# 02_POWER_BEEP_IrDA.net
KiCad netlist of a schematic drawn in Altium Designer
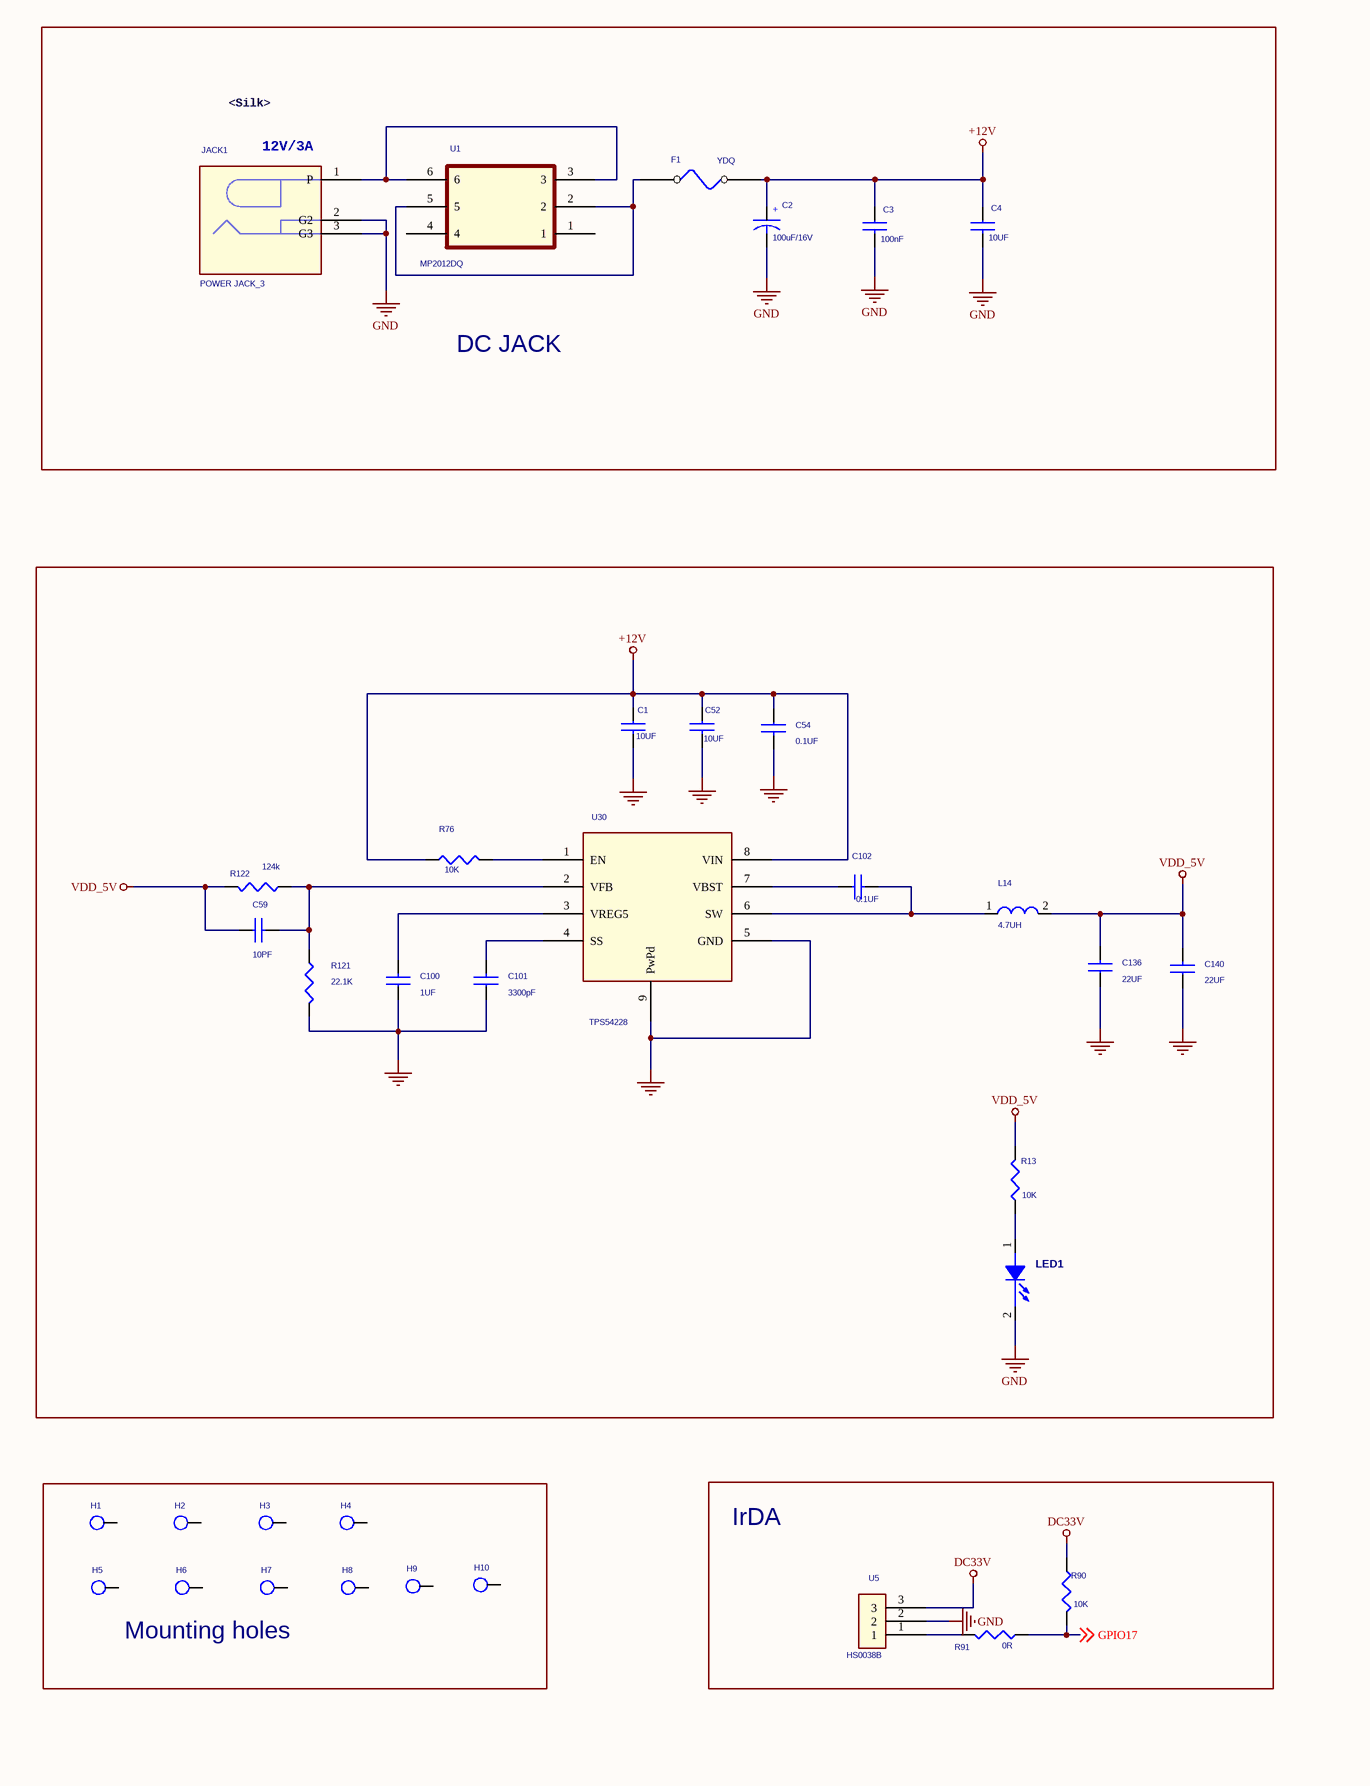
[diagram p0: 02 POWER,BEEP,IrDA.SchDoc, left]
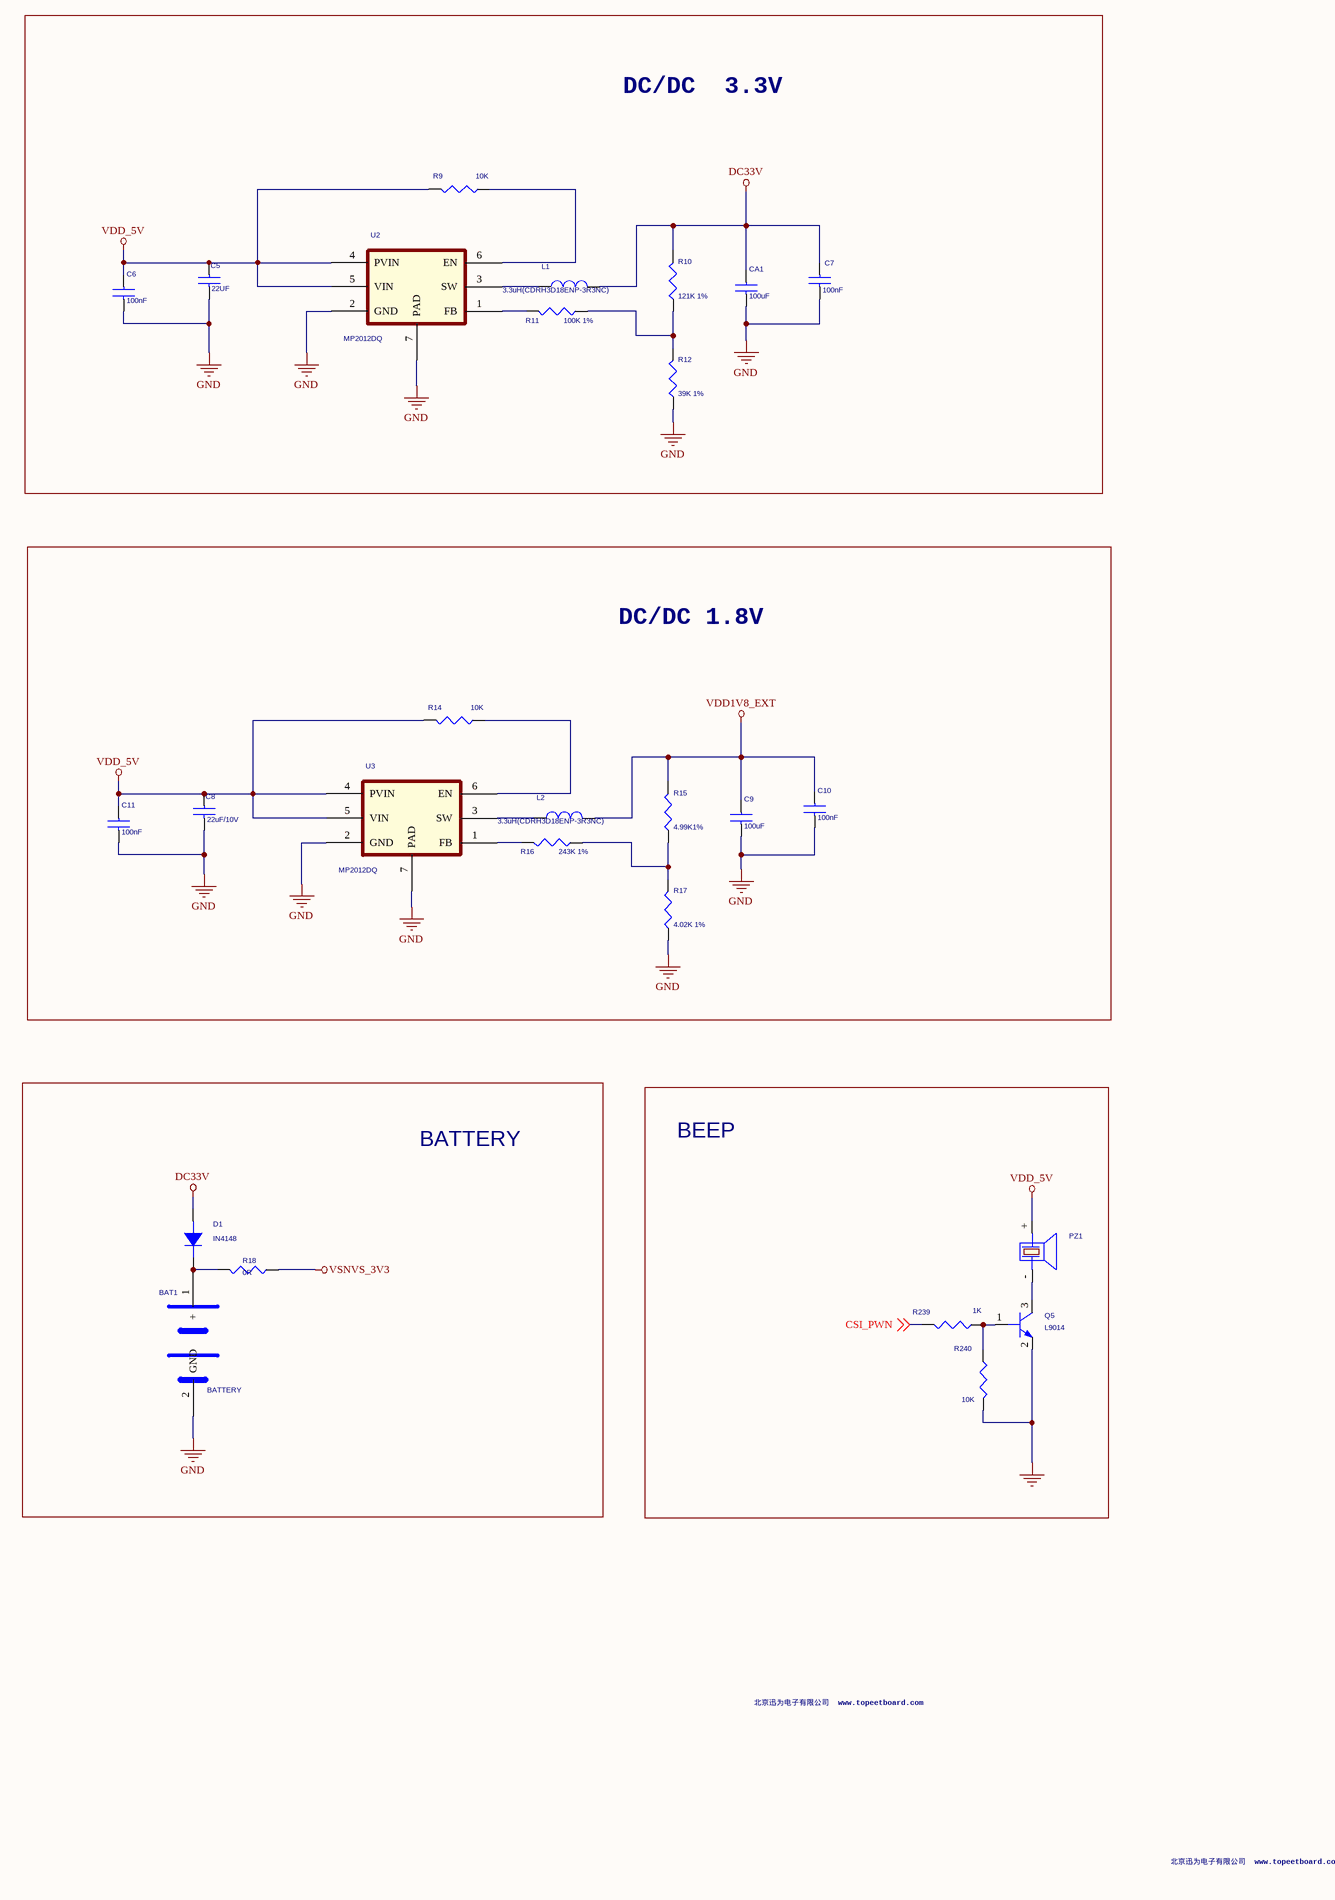
[diagram p1: 02 POWER,BEEP,IrDA.SchDoc, right]

(export (version "E")
  (design (tool "Eeschema 10.0.6"))
  (components
    (comp (ref "BAT1") (value "BATTERY") (footprint "BATTERY") (libsource (lib "*") (part "BATTERY_0")))
    (comp (ref "C1") (value "10UF") (libsource (lib "*") (part "CAP NP")))
    (comp (ref "C2") (value "100uF/16V") (footprint "T2012") (libsource (lib "*") (part "CT2012_0")))
    (comp (ref "C3") (value "100nF") (footprint "C1608") (libsource (lib "*") (part "C1608_Dup2")))
    (comp (ref "C4") (value "10UF") (footprint "C1608") (libsource (lib "*") (part "C1608_Dup2")))
    (comp (ref "C5") (value "22UF") (footprint "1206-A") (libsource (lib "*") (part "C1206_0")))
    (comp (ref "C6") (value "100nF") (footprint "C1608") (libsource (lib "*") (part "C1608_Dup2")))
    (comp (ref "C7") (value "100nF") (footprint "C1608") (libsource (lib "*") (part "C1608_Dup2")))
    (comp (ref "C8") (value "22uF/10V") (footprint "1206-A") (libsource (lib "*") (part "C1206_0")))
    (comp (ref "C9") (value "100uF") (footprint "C1608") (libsource (lib "*") (part "C1608_Dup2")))
    (comp (ref "C10") (value "100nF") (footprint "C1608") (libsource (lib "*") (part "C1608_Dup2")))
    (comp (ref "C11") (value "100nF") (footprint "C1608") (libsource (lib "*") (part "C1608_Dup2")))
    (comp (ref "C52") (value "10UF") (libsource (lib "*") (part "CAP NP")))
    (comp (ref "C54") (value "0.1UF") (libsource (lib "*") (part "CAP NP")))
    (comp (ref "C59") (value "10PF") (libsource (lib "*") (part "CAP NP")))
    (comp (ref "C100") (value "1UF") (libsource (lib "*") (part "CAP NP")))
    (comp (ref "C101") (value "3300pF") (libsource (lib "*") (part "CAP NP")))
    (comp (ref "C102") (value "0.1UF") (libsource (lib "*") (part "CAP NP")))
    (comp (ref "C136") (value "22UF") (libsource (lib "*") (part "CAP NP")))
    (comp (ref "C140") (value "22UF") (libsource (lib "*") (part "CAP NP")))
    (comp (ref "CA1") (value "100uF") (footprint "C1608") (libsource (lib "*") (part "C1608_Dup2")))
    (comp (ref "D1") (value "IN4148") (libsource (lib "*") (part "DIODE")))
    (comp (ref "F1") (value "YDQ") (libsource (lib "*") (part "FUSE")))
    (comp (ref "H1") (value "TP_P0_0.8_D0") (footprint "TP_08") (libsource (lib "*") (part "TP_P0_0.8_D0")))
    (comp (ref "H2") (value "TP_P0_0.8_D0") (footprint "TP_08") (libsource (lib "*") (part "TP_P0_0.8_D0")))
    (comp (ref "H3") (value "TP_P0_0.8_D0") (footprint "TP_08") (libsource (lib "*") (part "TP_P0_0.8_D0")))
    (comp (ref "H4") (value "TP_P0_0.8_D0") (footprint "TP_08") (libsource (lib "*") (part "TP_P0_0.8_D0")))
    (comp (ref "H5") (value "TP_P0_0.8_D0") (footprint "TP_08") (libsource (lib "*") (part "TP_P0_0.8_D0")))
    (comp (ref "H6") (value "TP_P0_0.8_D0") (footprint "TP_08") (libsource (lib "*") (part "TP_P0_0.8_D0")))
    (comp (ref "H7") (value "TP_P0_0.8_D0") (footprint "TP_08") (libsource (lib "*") (part "TP_P0_0.8_D0")))
    (comp (ref "H8") (value "TP_P0_0.8_D0") (footprint "TP_08") (libsource (lib "*") (part "TP_P0_0.8_D0")))
    (comp (ref "H9") (value "TP_P0_0.8_D0") (footprint "TP_08") (libsource (lib "*") (part "TP_P0_0.8_D0")))
    (comp (ref "H10") (value "TP_P0_0.8_D0") (footprint "TP_08") (libsource (lib "*") (part "TP_P0_0.8_D0")))
    (comp (ref "JACK1") (value "POWER JACK_3") (libsource (lib "*") (part "POWER JACK_3")))
    (comp (ref "L1")
      (value "3.3uH(CDRH3D18ENP-3R3NC)")
      (footprint "LQH32C")
      (libsource (lib "*") (part "LQH32C_0_Dup2"))
    )
    (comp (ref "L2")
      (value "3.3uH(CDRH3D18ENP-3R3NC)")
      (footprint "LQH32C")
      (libsource (lib "*") (part "LQH32C_0_Dup2"))
    )
    (comp (ref "L14") (value "4.7UH") (footprint "LQH32C") (libsource (lib "*") (part "LQH32C_0_Dup1")))
    (comp (ref "LED1")
      (value "LED-Red (SMD 2012)")
      (footprint "LED-3216")
      (libsource (lib "*") (part "LED-RED_SMD_1"))
    )
    (comp (ref "PZ1") (value "PIEZO BUZZER_2") (libsource (lib "*") (part "PIEZO BUZZER_2")))
    (comp (ref "Q5") (value "L9014") (libsource (lib "*") (part "L14P2/TO_1")))
    (comp (ref "R9") (value "10K") (footprint "R1005") (libsource (lib "*") (part "R1005_0_Dup2")))
    (comp (ref "R10") (value "121K 1%") (footprint "R1005") (libsource (lib "*") (part "R1005_0_Dup2")))
    (comp (ref "R11") (value "100K 1%") (footprint "R1005") (libsource (lib "*") (part "R1005_0_Dup2")))
    (comp (ref "R12") (value "39K 1%") (footprint "R1005") (libsource (lib "*") (part "R1005_0_Dup2")))
    (comp (ref "R13") (value "10K") (footprint "R1005") (libsource (lib "*") (part "R1005_0_Dup2")))
    (comp (ref "R14") (value "10K") (footprint "R1005") (libsource (lib "*") (part "R1005_0_Dup2")))
    (comp (ref "R15") (value "4.99K1%") (footprint "R1005") (libsource (lib "*") (part "R1005_0_Dup2")))
    (comp (ref "R16") (value "243K 1%") (footprint "R1005") (libsource (lib "*") (part "R1005_0_Dup2")))
    (comp (ref "R17") (value "4.02K 1%") (footprint "R1005") (libsource (lib "*") (part "R1005_0_Dup2")))
    (comp (ref "R18") (value "0R") (libsource (lib "*") (part "R_Dup1")))
    (comp (ref "R76") (value "10K") (libsource (lib "*") (part "R_Dup1")))
    (comp (ref "R90") (value "10K") (libsource (lib "*") (part "R_Dup1")))
    (comp (ref "R91") (value "0R") (libsource (lib "*") (part "R_Dup1")))
    (comp (ref "R121") (value "22.1K") (libsource (lib "*") (part "R_Dup1")))
    (comp (ref "R122") (value "124k") (libsource (lib "*") (part "R_Dup1")))
    (comp (ref "R239") (value "1K") (libsource (lib "*") (part "R_Dup1")))
    (comp (ref "R240") (value "10K") (libsource (lib "*") (part "R_Dup1")))
    (comp (ref "U1") (value "MP2012DQ") (footprint "QFN6") (libsource (lib "*") (part "U-MP2012DQ_0")))
    (comp (ref "U2") (value "MP2012DQ") (footprint "QFN6") (libsource (lib "*") (part "U-MP2012DQ")))
    (comp (ref "U3") (value "MP2012DQ") (footprint "QFN6") (libsource (lib "*") (part "U-MP2012DQ")))
    (comp (ref "U5") (value "HS0038B") (libsource (lib "*") (part "HS0038")))
    (comp (ref "U30") (value "TPS54228") (libsource (lib "*") (part "RT8065_5")))
  )
  (nets
    (net (code "1") (name "+12V") (class "Default")
      (node (ref "C1") (pin "1") (pinfunction "1_1") (pintype "passive"))
      (node (ref "C2") (pin "1") (pinfunction "1_1") (pintype "passive"))
      (node (ref "C3") (pin "1") (pinfunction "1_1") (pintype "passive"))
      (node (ref "C4") (pin "1") (pinfunction "1_1") (pintype "passive"))
      (node (ref "C52") (pin "1") (pinfunction "1_1") (pintype "passive"))
      (node (ref "C54") (pin "1") (pinfunction "1_1") (pintype "passive"))
      (node (ref "F1") (pin "2") (pinfunction "2_2") (pintype "passive"))
      (node (ref "R76") (pin "1") (pinfunction "1_1") (pintype "passive"))
      (node (ref "U30") (pin "8") (pinfunction "VIN_8") (pintype "passive"))
    )
    (net (code "2") (name "CSI_PWN") (class "Default")
      (node (ref "R239") (pin "2") (pinfunction "2_2") (pintype "passive"))
    )
    (net (code "3") (name "DC33V") (class "Default")
      (node (ref "C7") (pin "1") (pinfunction "1_1") (pintype "passive"))
      (node (ref "CA1") (pin "1") (pinfunction "1_1") (pintype "passive"))
      (node (ref "D1") (pin "1") (pinfunction "A_1") (pintype "passive"))
      (node (ref "L1") (pin "2") (pinfunction "2_2") (pintype "passive"))
      (node (ref "R10") (pin "2") (pinfunction "2_2") (pintype "passive"))
      (node (ref "R90") (pin "1") (pinfunction "1_1") (pintype "passive"))
      (node (ref "U5") (pin "3") (pinfunction "3_3") (pintype "passive"))
    )
    (net (code "4") (name "GND") (class "Default")
      (node (ref "BAT1") (pin "2") (pinfunction "GND_2") (pintype "passive"))
      (node (ref "C1") (pin "2") (pinfunction "2_2") (pintype "passive"))
      (node (ref "C10") (pin "2") (pinfunction "2_2") (pintype "passive"))
      (node (ref "C100") (pin "1") (pinfunction "1_1") (pintype "passive"))
      (node (ref "C101") (pin "1") (pinfunction "1_1") (pintype "passive"))
      (node (ref "C11") (pin "2") (pinfunction "2_2") (pintype "passive"))
      (node (ref "C136") (pin "1") (pinfunction "1_1") (pintype "passive"))
      (node (ref "C140") (pin "1") (pinfunction "1_1") (pintype "passive"))
      (node (ref "C2") (pin "2") (pinfunction "2_2") (pintype "passive"))
      (node (ref "C3") (pin "2") (pinfunction "2_2") (pintype "passive"))
      (node (ref "C4") (pin "2") (pinfunction "2_2") (pintype "passive"))
      (node (ref "C5") (pin "2") (pinfunction "2_2") (pintype "passive"))
      (node (ref "C52") (pin "2") (pinfunction "2_2") (pintype "passive"))
      (node (ref "C54") (pin "2") (pinfunction "2_2") (pintype "passive"))
      (node (ref "C6") (pin "2") (pinfunction "2_2") (pintype "passive"))
      (node (ref "C7") (pin "2") (pinfunction "2_2") (pintype "passive"))
      (node (ref "C8") (pin "2") (pinfunction "2_2") (pintype "passive"))
      (node (ref "C9") (pin "2") (pinfunction "2_2") (pintype "passive"))
      (node (ref "CA1") (pin "2") (pinfunction "2_2") (pintype "passive"))
      (node (ref "JACK1") (pin "2") (pinfunction "G2_2") (pintype "passive"))
      (node (ref "JACK1") (pin "3") (pinfunction "G3_3") (pintype "passive"))
      (node (ref "LED1") (pin "2") (pinfunction "CATHODE_2") (pintype "passive"))
      (node (ref "Q5") (pin "2") (pinfunction "EMITTER_2") (pintype "passive"))
      (node (ref "R12") (pin "1") (pinfunction "1_1") (pintype "passive"))
      (node (ref "R121") (pin "2") (pinfunction "2_2") (pintype "passive"))
      (node (ref "R17") (pin "1") (pinfunction "1_1") (pintype "passive"))
      (node (ref "R240") (pin "2") (pinfunction "2_2") (pintype "passive"))
      (node (ref "U2") (pin "2") (pinfunction "GND_2") (pintype "passive"))
      (node (ref "U2") (pin "7") (pinfunction "PAD_7") (pintype "passive"))
      (node (ref "U3") (pin "2") (pinfunction "GND_2") (pintype "passive"))
      (node (ref "U3") (pin "7") (pinfunction "PAD_7") (pintype "passive"))
      (node (ref "U30") (pin "5") (pinfunction "GND_5") (pintype "passive"))
      (node (ref "U30") (pin "9") (pinfunction "PwPd_9") (pintype "passive"))
      (node (ref "U5") (pin "2") (pinfunction "2_2") (pintype "passive"))
    )
    (net (code "5") (name "GPIO17") (class "Default")
      (node (ref "R90") (pin "2") (pinfunction "2_2") (pintype "passive"))
      (node (ref "R91") (pin "1") (pinfunction "1_1") (pintype "passive"))
    )
    (net (code "6") (name "Net-(BAT1-+)") (class "Default")
      (node (ref "BAT1") (pin "1") (pinfunction "+_1") (pintype "passive"))
      (node (ref "D1") (pin "2") (pinfunction "K_2") (pintype "passive"))
      (node (ref "R18") (pin "2") (pinfunction "2_2") (pintype "passive"))
    )
    (net (code "7") (name "Net-(F1-Pad1)") (class "Default")
      (node (ref "F1") (pin "1") (pinfunction "1_1") (pintype "passive"))
      (node (ref "U1") (pin "2") (pinfunction "2_2") (pintype "passive"))
      (node (ref "U1") (pin "5") (pinfunction "5_5") (pintype "passive"))
    )
    (net (code "8") (name "Net-(JACK1-P)") (class "Default")
      (node (ref "JACK1") (pin "1") (pinfunction "P_1") (pintype "passive"))
      (node (ref "U1") (pin "3") (pinfunction "3_3") (pintype "passive"))
      (node (ref "U1") (pin "6") (pinfunction "6_6") (pintype "passive"))
    )
    (net (code "9") (name "Net-(LED1-ANODE)") (class "Default")
      (node (ref "LED1") (pin "1") (pinfunction "ANODE_1") (pintype "passive"))
      (node (ref "R13") (pin "1") (pinfunction "1_1") (pintype "passive"))
    )
    (net (code "10") (name "Net-(Q5-BASE)") (class "Default")
      (node (ref "Q5") (pin "1") (pinfunction "BASE_1") (pintype "passive"))
      (node (ref "R239") (pin "1") (pinfunction "1_1") (pintype "passive"))
      (node (ref "R240") (pin "1") (pinfunction "1_1") (pintype "passive"))
    )
    (net (code "11") (name "Net-(Q5-COLLECTOR)") (class "Default")
      (node (ref "PZ1") (pin "-") (pinfunction "-_-") (pintype "passive"))
      (node (ref "Q5") (pin "3") (pinfunction "COLLECTOR_3") (pintype "passive"))
    )
    (net (code "12") (name "Net-(R10-Pad1)") (class "Default")
      (node (ref "R10") (pin "1") (pinfunction "1_1") (pintype "passive"))
      (node (ref "R11") (pin "1") (pinfunction "1_1") (pintype "passive"))
      (node (ref "R12") (pin "2") (pinfunction "2_2") (pintype "passive"))
    )
    (net (code "13") (name "Net-(R15-Pad1)") (class "Default")
      (node (ref "R15") (pin "1") (pinfunction "1_1") (pintype "passive"))
      (node (ref "R16") (pin "1") (pinfunction "1_1") (pintype "passive"))
      (node (ref "R17") (pin "2") (pinfunction "2_2") (pintype "passive"))
    )
    (net (code "14") (name "Net-(R91-Pad2)") (class "Default")
      (node (ref "R91") (pin "2") (pinfunction "2_2") (pintype "passive"))
      (node (ref "U5") (pin "1") (pinfunction "1_1") (pintype "passive"))
    )
    (net (code "15") (name "Net-(U2-EN)") (class "Default")
      (node (ref "R9") (pin "1") (pinfunction "1_1") (pintype "passive"))
      (node (ref "U2") (pin "6") (pinfunction "EN_6") (pintype "passive"))
    )
    (net (code "16") (name "Net-(U2-FB)") (class "Default")
      (node (ref "R11") (pin "2") (pinfunction "2_2") (pintype "passive"))
      (node (ref "U2") (pin "1") (pinfunction "FB_1") (pintype "passive"))
    )
    (net (code "17") (name "Net-(U2-SW)") (class "Default")
      (node (ref "L1") (pin "1") (pinfunction "1_1") (pintype "passive"))
      (node (ref "U2") (pin "3") (pinfunction "SW_3") (pintype "passive"))
    )
    (net (code "18") (name "Net-(U3-EN)") (class "Default")
      (node (ref "R14") (pin "1") (pinfunction "1_1") (pintype "passive"))
      (node (ref "U3") (pin "6") (pinfunction "EN_6") (pintype "passive"))
    )
    (net (code "19") (name "Net-(U3-FB)") (class "Default")
      (node (ref "R16") (pin "2") (pinfunction "2_2") (pintype "passive"))
      (node (ref "U3") (pin "1") (pinfunction "FB_1") (pintype "passive"))
    )
    (net (code "20") (name "Net-(U3-SW)") (class "Default")
      (node (ref "L2") (pin "1") (pinfunction "1_1") (pintype "passive"))
      (node (ref "U3") (pin "3") (pinfunction "SW_3") (pintype "passive"))
    )
    (net (code "21") (name "Net-(U30-EN)") (class "Default")
      (node (ref "R76") (pin "2") (pinfunction "2_2") (pintype "passive"))
      (node (ref "U30") (pin "1") (pinfunction "EN_1") (pintype "passive"))
    )
    (net (code "22") (name "Net-(U30-SS)") (class "Default")
      (node (ref "C101") (pin "2") (pinfunction "2_2") (pintype "passive"))
      (node (ref "U30") (pin "4") (pinfunction "SS_4") (pintype "passive"))
    )
    (net (code "23") (name "Net-(U30-SW)") (class "Default")
      (node (ref "C102") (pin "2") (pinfunction "2_2") (pintype "passive"))
      (node (ref "L14") (pin "1") (pinfunction "1_1") (pintype "passive"))
      (node (ref "U30") (pin "6") (pinfunction "SW_6") (pintype "passive"))
    )
    (net (code "24") (name "Net-(U30-VBST)") (class "Default")
      (node (ref "C102") (pin "1") (pinfunction "1_1") (pintype "passive"))
      (node (ref "U30") (pin "7") (pinfunction "VBST_7") (pintype "passive"))
    )
    (net (code "25") (name "Net-(U30-VFB)") (class "Default")
      (node (ref "C59") (pin "2") (pinfunction "2_2") (pintype "passive"))
      (node (ref "R121") (pin "1") (pinfunction "1_1") (pintype "passive"))
      (node (ref "R122") (pin "1") (pinfunction "1_1") (pintype "passive"))
      (node (ref "U30") (pin "2") (pinfunction "VFB_2") (pintype "passive"))
    )
    (net (code "26") (name "Net-(U30-VREG5)") (class "Default")
      (node (ref "C100") (pin "2") (pinfunction "2_2") (pintype "passive"))
      (node (ref "U30") (pin "3") (pinfunction "VREG5_3") (pintype "passive"))
    )
    (net (code "27") (name "VDD1V8_EXT") (class "Default")
      (node (ref "C10") (pin "1") (pinfunction "1_1") (pintype "passive"))
      (node (ref "C9") (pin "1") (pinfunction "1_1") (pintype "passive"))
      (node (ref "L2") (pin "2") (pinfunction "2_2") (pintype "passive"))
      (node (ref "R15") (pin "2") (pinfunction "2_2") (pintype "passive"))
    )
    (net (code "28") (name "VDD_5V") (class "Default")
      (node (ref "C11") (pin "1") (pinfunction "1_1") (pintype "passive"))
      (node (ref "C136") (pin "2") (pinfunction "2_2") (pintype "passive"))
      (node (ref "C140") (pin "2") (pinfunction "2_2") (pintype "passive"))
      (node (ref "C5") (pin "1") (pinfunction "1_1") (pintype "passive"))
      (node (ref "C59") (pin "1") (pinfunction "1_1") (pintype "passive"))
      (node (ref "C6") (pin "1") (pinfunction "1_1") (pintype "passive"))
      (node (ref "C8") (pin "1") (pinfunction "1_1") (pintype "passive"))
      (node (ref "L14") (pin "2") (pinfunction "2_2") (pintype "passive"))
      (node (ref "PZ1") (pin "+") (pinfunction "+_+") (pintype "passive"))
      (node (ref "R122") (pin "2") (pinfunction "2_2") (pintype "passive"))
      (node (ref "R13") (pin "2") (pinfunction "2_2") (pintype "passive"))
      (node (ref "R14") (pin "2") (pinfunction "2_2") (pintype "passive"))
      (node (ref "R9") (pin "2") (pinfunction "2_2") (pintype "passive"))
      (node (ref "U2") (pin "4") (pinfunction "PVIN_4") (pintype "passive"))
      (node (ref "U2") (pin "5") (pinfunction "VIN_5") (pintype "passive"))
      (node (ref "U3") (pin "4") (pinfunction "PVIN_4") (pintype "passive"))
      (node (ref "U3") (pin "5") (pinfunction "VIN_5") (pintype "passive"))
    )
    (net (code "29") (name "VSNVS_3V3") (class "Default")
      (node (ref "R18") (pin "1") (pinfunction "1_1") (pintype "passive"))
    )
    (net (code "30") (name "unconnected-(H1-Pad1)") (class "Default")
      (node (ref "H1") (pin "1") (pinfunction "1_1") (pintype "passive"))
    )
    (net (code "31") (name "unconnected-(H2-Pad1)") (class "Default")
      (node (ref "H2") (pin "1") (pinfunction "1_1") (pintype "passive"))
    )
    (net (code "32") (name "unconnected-(H3-Pad1)") (class "Default")
      (node (ref "H3") (pin "1") (pinfunction "1_1") (pintype "passive"))
    )
    (net (code "33") (name "unconnected-(H4-Pad1)") (class "Default")
      (node (ref "H4") (pin "1") (pinfunction "1_1") (pintype "passive"))
    )
    (net (code "34") (name "unconnected-(H5-Pad1)") (class "Default")
      (node (ref "H5") (pin "1") (pinfunction "1_1") (pintype "passive"))
    )
    (net (code "35") (name "unconnected-(H6-Pad1)") (class "Default")
      (node (ref "H6") (pin "1") (pinfunction "1_1") (pintype "passive"))
    )
    (net (code "36") (name "unconnected-(H7-Pad1)") (class "Default")
      (node (ref "H7") (pin "1") (pinfunction "1_1") (pintype "passive"))
    )
    (net (code "37") (name "unconnected-(H8-Pad1)") (class "Default")
      (node (ref "H8") (pin "1") (pinfunction "1_1") (pintype "passive"))
    )
    (net (code "38") (name "unconnected-(H9-Pad1)") (class "Default")
      (node (ref "H9") (pin "1") (pinfunction "1_1") (pintype "passive"))
    )
    (net (code "39") (name "unconnected-(H10-Pad1)") (class "Default")
      (node (ref "H10") (pin "1") (pinfunction "1_1") (pintype "passive"))
    )
    (net (code "40") (name "unconnected-(U1-Pad1)") (class "Default")
      (node (ref "U1") (pin "1") (pinfunction "1_1") (pintype "passive"))
    )
    (net (code "41") (name "unconnected-(U1-Pad4)") (class "Default")
      (node (ref "U1") (pin "4") (pinfunction "4_4") (pintype "passive"))
    )
  )
)
